# USB_HS_PHY.net
KiCad netlist of a schematic drawn in Altium Designer
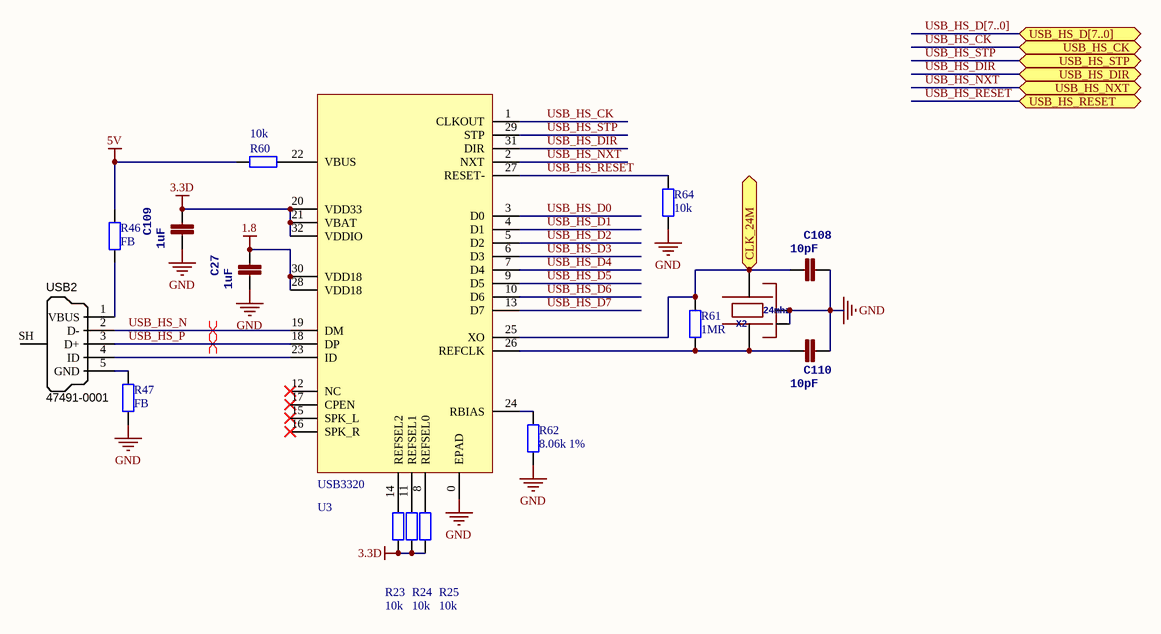
[diagram p0: USB_HS_PHY.SchDoc]

(export (version "E")
  (design (tool "Eeschema 10.0.6"))
  (components
    (comp (ref "C27")
      (value "1uF")
      (footprint "0402")
      (description "<b>Capacitor</b>\nStandard 0603 ceramic capacitor, and 0.1\" leaded capacitor.")
      (fields (field (name "PARTNO") "CC0402ZRY5V7BB104"))
      (libsource (lib "pixhawk2") (part "CAP0402-CAP"))
    )
    (comp (ref "C108")
      (value "10pF")
      (footprint "0402")
      (description "<b>Capacitor</b>\nStandard 0603 ceramic capacitor, and 0.1\" leaded capacitor.")
      (fields (field (name "PARTNO") "CC0402ZRY5V7BB104"))
      (libsource (lib "") (part "CAP0402-CAP_1"))
    )
    (comp (ref "C109")
      (value "1uF")
      (footprint "0402")
      (description "<b>Capacitor</b>\nStandard 0603 ceramic capacitor, and 0.1\" leaded capacitor.")
      (fields (field (name "PARTNO") "CC0402ZRY5V7BB104"))
      (libsource (lib "pixhawk2") (part "CAP0402-CAP"))
    )
    (comp (ref "C110")
      (value "10pF")
      (footprint "0402")
      (description "<b>Capacitor</b>\nStandard 0603 ceramic capacitor, and 0.1\" leaded capacitor.")
      (fields (field (name "PARTNO") "CC0402ZRY5V7BB104"))
      (libsource (lib "*") (part "CAP0402-CAP"))
    )
    (comp (ref "R23")
      (value "10k")
      (footprint "0402")
      (description "Resistor")
      (fields (field (name "PUBLISHER") "Altium Limited"))
      (libsource (lib "Miscellaneous Devices") (part "Res2"))
    )
    (comp (ref "R24")
      (value "10k")
      (footprint "0402")
      (description "Resistor")
      (fields (field (name "PUBLISHER") "Altium Limited"))
      (libsource (lib "Miscellaneous Devices") (part "Res2"))
    )
    (comp (ref "R25")
      (value "10k")
      (footprint "0402")
      (description "Resistor")
      (fields (field (name "PUBLISHER") "Altium Limited"))
      (libsource (lib "Miscellaneous Devices") (part "Res2"))
    )
    (comp (ref "R46")
      (value "FB")
      (footprint "0603")
      (description "Resistor")
      (fields (field (name "PUBLISHER") "Altium Limited"))
      (libsource (lib "Miscellaneous Devices") (part "Res2"))
    )
    (comp (ref "R47")
      (value "FB")
      (footprint "0603")
      (description "Resistor")
      (fields (field (name "PUBLISHER") "Altium Limited"))
      (libsource (lib "Miscellaneous Devices") (part "Res2"))
    )
    (comp (ref "R60")
      (value "10k")
      (footprint "0402")
      (description "Resistor")
      (fields (field (name "PUBLISHER") "Altium Limited"))
      (libsource (lib "") (part "Res2_1"))
    )
    (comp (ref "R61")
      (value "1MR")
      (footprint "0402")
      (description "Resistor")
      (fields (field (name "PUBLISHER") "Altium Limited"))
      (libsource (lib "") (part "Res2_2"))
    )
    (comp (ref "R62")
      (value "8.06k 1%")
      (footprint "0402")
      (description "Resistor")
      (fields (field (name "PUBLISHER") "Altium Limited"))
      (libsource (lib "") (part "Res2_2"))
    )
    (comp (ref "R64")
      (value "10k")
      (footprint "0402")
      (description "Resistor")
      (fields (field (name "PUBLISHER") "Altium Limited"))
      (libsource (lib "Miscellaneous Devices") (part "Res2"))
    )
    (comp (ref "U3") (value "USB3320") (footprint "USB3300") (libsource (lib "F4SDR") (part "USB3320")))
    (comp (ref "USB2")
      (value "USB Micro Type B")
      (footprint "MICRO-YZX")
      (description "Connector SMD USB Micro Type B middle mount")
      (fields (field (name "MANUFACTURER PART NUMBER 1") "47491-0001"))
      (libsource (lib "PBL - Connectors") (part "USB_Micro_TypeB"))
    )
    (comp (ref "X2")
      (value "24mhz")
      (footprint "OSCILLATOR-3.2X2.5")
      (description "Crystal Oscillator in 3.2x2.5 SMD")
      (libsource (lib "sch") (part "OSCILLATOR-3.2X2.5"))
    )
  )
  (nets
    (net (code "1") (name "/CLK_24M") (class "Default")
      (node (ref "C108") (pin "2") (pinfunction "2_2") (pintype "passive"))
      (node (ref "R61") (pin "2") (pinfunction "2_2") (pintype "passive"))
      (node (ref "U3") (pin "25") (pinfunction "XO_25") (pintype "passive"))
      (node (ref "X2") (pin "3") (pinfunction "3_3") (pintype "passive"))
    )
    (net (code "2") (name "/USB_HS_CK") (class "Default")
      (node (ref "U3") (pin "1") (pinfunction "CLKOUT_1") (pintype "passive"))
    )
    (net (code "3") (name "/USB_HS_D0") (class "Default")
      (node (ref "U3") (pin "3") (pinfunction "D0_3") (pintype "passive"))
    )
    (net (code "4") (name "/USB_HS_D1") (class "Default")
      (node (ref "U3") (pin "4") (pinfunction "D1_4") (pintype "passive"))
    )
    (net (code "5") (name "/USB_HS_D2") (class "Default")
      (node (ref "U3") (pin "5") (pinfunction "D2_5") (pintype "passive"))
    )
    (net (code "6") (name "/USB_HS_D3") (class "Default")
      (node (ref "U3") (pin "6") (pinfunction "D3_6") (pintype "passive"))
    )
    (net (code "7") (name "/USB_HS_D4") (class "Default")
      (node (ref "U3") (pin "7") (pinfunction "D4_7") (pintype "passive"))
    )
    (net (code "8") (name "/USB_HS_D5") (class "Default")
      (node (ref "U3") (pin "9") (pinfunction "D5_9") (pintype "passive"))
    )
    (net (code "9") (name "/USB_HS_D6") (class "Default")
      (node (ref "U3") (pin "10") (pinfunction "D6_10") (pintype "passive"))
    )
    (net (code "10") (name "/USB_HS_D7") (class "Default")
      (node (ref "U3") (pin "13") (pinfunction "D7_13") (pintype "passive"))
    )
    (net (code "11") (name "/USB_HS_DIR") (class "Default")
      (node (ref "U3") (pin "31") (pinfunction "DIR_31") (pintype "passive"))
    )
    (net (code "13") (name "/USB_HS_N") (class "Default")
      (node (ref "U3") (pin "19") (pinfunction "DM_19") (pintype "passive"))
      (node (ref "USB2") (pin "2") (pinfunction "D-_2") (pintype "passive"))
    )
    (net (code "14") (name "/USB_HS_NXT") (class "Default")
      (node (ref "U3") (pin "2") (pinfunction "NXT_2") (pintype "passive"))
    )
    (net (code "15") (name "/USB_HS_P") (class "Default")
      (node (ref "U3") (pin "18") (pinfunction "DP_18") (pintype "passive"))
      (node (ref "USB2") (pin "3") (pinfunction "D+_3") (pintype "passive"))
    )
    (net (code "16") (name "/USB_HS_RESET") (class "Default")
      (node (ref "R64") (pin "1") (pinfunction "1_1") (pintype "passive"))
      (node (ref "U3") (pin "27") (pinfunction "RESET-_27") (pintype "passive"))
    )
    (net (code "17") (name "/USB_HS_STP") (class "Default")
      (node (ref "U3") (pin "29") (pinfunction "STP_29") (pintype "passive"))
    )
    (net (code "18") (name "1.8") (class "Default")
      (node (ref "C27") (pin "1") (pinfunction "1_1") (pintype "passive"))
      (node (ref "U3") (pin "28") (pinfunction "VDD18_28") (pintype "passive"))
      (node (ref "U3") (pin "30") (pinfunction "VDD18_30") (pintype "passive"))
    )
    (net (code "19") (name "3.3D") (class "Default")
      (node (ref "C109") (pin "1") (pinfunction "1_1") (pintype "passive"))
      (node (ref "R23") (pin "2") (pinfunction "2_2") (pintype "passive"))
      (node (ref "R24") (pin "2") (pinfunction "2_2") (pintype "passive"))
      (node (ref "R25") (pin "2") (pinfunction "2_2") (pintype "passive"))
      (node (ref "U3") (pin "20") (pinfunction "VDD33_20") (pintype "passive"))
      (node (ref "U3") (pin "21") (pinfunction "VBAT_21") (pintype "passive"))
      (node (ref "U3") (pin "32") (pinfunction "VDDIO_32") (pintype "passive"))
    )
    (net (code "20") (name "5V") (class "Default")
      (node (ref "R46") (pin "1") (pinfunction "1_1") (pintype "passive"))
      (node (ref "R60") (pin "1") (pinfunction "1_1") (pintype "passive"))
    )
    (net (code "21") (name "GND") (class "Default")
      (node (ref "C108") (pin "1") (pinfunction "1_1") (pintype "passive"))
      (node (ref "C109") (pin "2") (pinfunction "2_2") (pintype "passive"))
      (node (ref "C110") (pin "1") (pinfunction "1_1") (pintype "passive"))
      (node (ref "C27") (pin "2") (pinfunction "2_2") (pintype "passive"))
      (node (ref "R47") (pin "2") (pinfunction "2_2") (pintype "passive"))
      (node (ref "R62") (pin "1") (pinfunction "1_1") (pintype "passive"))
      (node (ref "R64") (pin "2") (pinfunction "2_2") (pintype "passive"))
      (node (ref "U3") (pin "0") (pinfunction "EPAD_0") (pintype "passive"))
      (node (ref "X2") (pin "2") (pinfunction "NC_2_2") (pintype "open_emitter"))
      (node (ref "X2") (pin "4") (pinfunction "NC_4_4") (pintype "open_emitter"))
    )
    (net (code "22") (name "Net-(U3-ID)") (class "Default")
      (node (ref "U3") (pin "23") (pinfunction "ID_23") (pintype "passive"))
      (node (ref "USB2") (pin "4") (pinfunction "ID_4") (pintype "passive"))
    )
    (net (code "23") (name "Net-(U3-RBIAS)") (class "Default")
      (node (ref "R62") (pin "2") (pinfunction "2_2") (pintype "passive"))
      (node (ref "U3") (pin "24") (pinfunction "RBIAS_24") (pintype "passive"))
    )
    (net (code "24") (name "Net-(U3-REFCLK)") (class "Default")
      (node (ref "C110") (pin "2") (pinfunction "2_2") (pintype "passive"))
      (node (ref "R61") (pin "1") (pinfunction "1_1") (pintype "passive"))
      (node (ref "U3") (pin "26") (pinfunction "REFCLK_26") (pintype "passive"))
      (node (ref "X2") (pin "1") (pinfunction "1_1") (pintype "passive"))
    )
    (net (code "25") (name "Net-(U3-REFSEL0)") (class "Default")
      (node (ref "R25") (pin "1") (pinfunction "1_1") (pintype "passive"))
      (node (ref "U3") (pin "8") (pinfunction "REFSEL0_8") (pintype "passive"))
    )
    (net (code "26") (name "Net-(U3-REFSEL1)") (class "Default")
      (node (ref "R24") (pin "1") (pinfunction "1_1") (pintype "passive"))
      (node (ref "U3") (pin "11") (pinfunction "REFSEL1_11") (pintype "passive"))
    )
    (net (code "27") (name "Net-(U3-REFSEL2)") (class "Default")
      (node (ref "R23") (pin "1") (pinfunction "1_1") (pintype "passive"))
      (node (ref "U3") (pin "14") (pinfunction "REFSEL2_14") (pintype "passive"))
    )
    (net (code "28") (name "Net-(U3-VBUS)") (class "Default")
      (node (ref "R60") (pin "2") (pinfunction "2_2") (pintype "passive"))
      (node (ref "U3") (pin "22") (pinfunction "VBUS_22") (pintype "passive"))
    )
    (net (code "29") (name "Net-(USB2-GND)") (class "Default")
      (node (ref "R47") (pin "1") (pinfunction "1_1") (pintype "passive"))
      (node (ref "USB2") (pin "5") (pinfunction "GND_5") (pintype "passive"))
    )
    (net (code "30") (name "Net-(USB2-VBUS)") (class "Default")
      (node (ref "R46") (pin "2") (pinfunction "2_2") (pintype "passive"))
      (node (ref "USB2") (pin "1") (pinfunction "VBUS_1") (pintype "passive"))
    )
    (net (code "31") (name "unconnected-(U3-CPEN-Pad17)") (class "Default")
      (node (ref "U3") (pin "17") (pinfunction "CPEN_17") (pintype "passive+no_connect"))
    )
    (net (code "32") (name "unconnected-(U3-NC-Pad12)") (class "Default")
      (node (ref "U3") (pin "12") (pinfunction "NC_12") (pintype "passive+no_connect"))
    )
    (net (code "33") (name "unconnected-(U3-SPK_L-Pad15)") (class "Default")
      (node (ref "U3") (pin "15") (pinfunction "SPK_L_15") (pintype "passive+no_connect"))
    )
    (net (code "34") (name "unconnected-(U3-SPK_R-Pad16)") (class "Default")
      (node (ref "U3") (pin "16") (pinfunction "SPK_R_16") (pintype "passive+no_connect"))
    )
    (net (code "35") (name "unconnected-(USB2-Shell-PadSH)") (class "Default")
      (node (ref "USB2") (pin "SH") (pinfunction "Shell_SH") (pintype "passive"))
    )
  )
)
